# Power_Management.net
KiCad netlist of a schematic drawn in Altium Designer
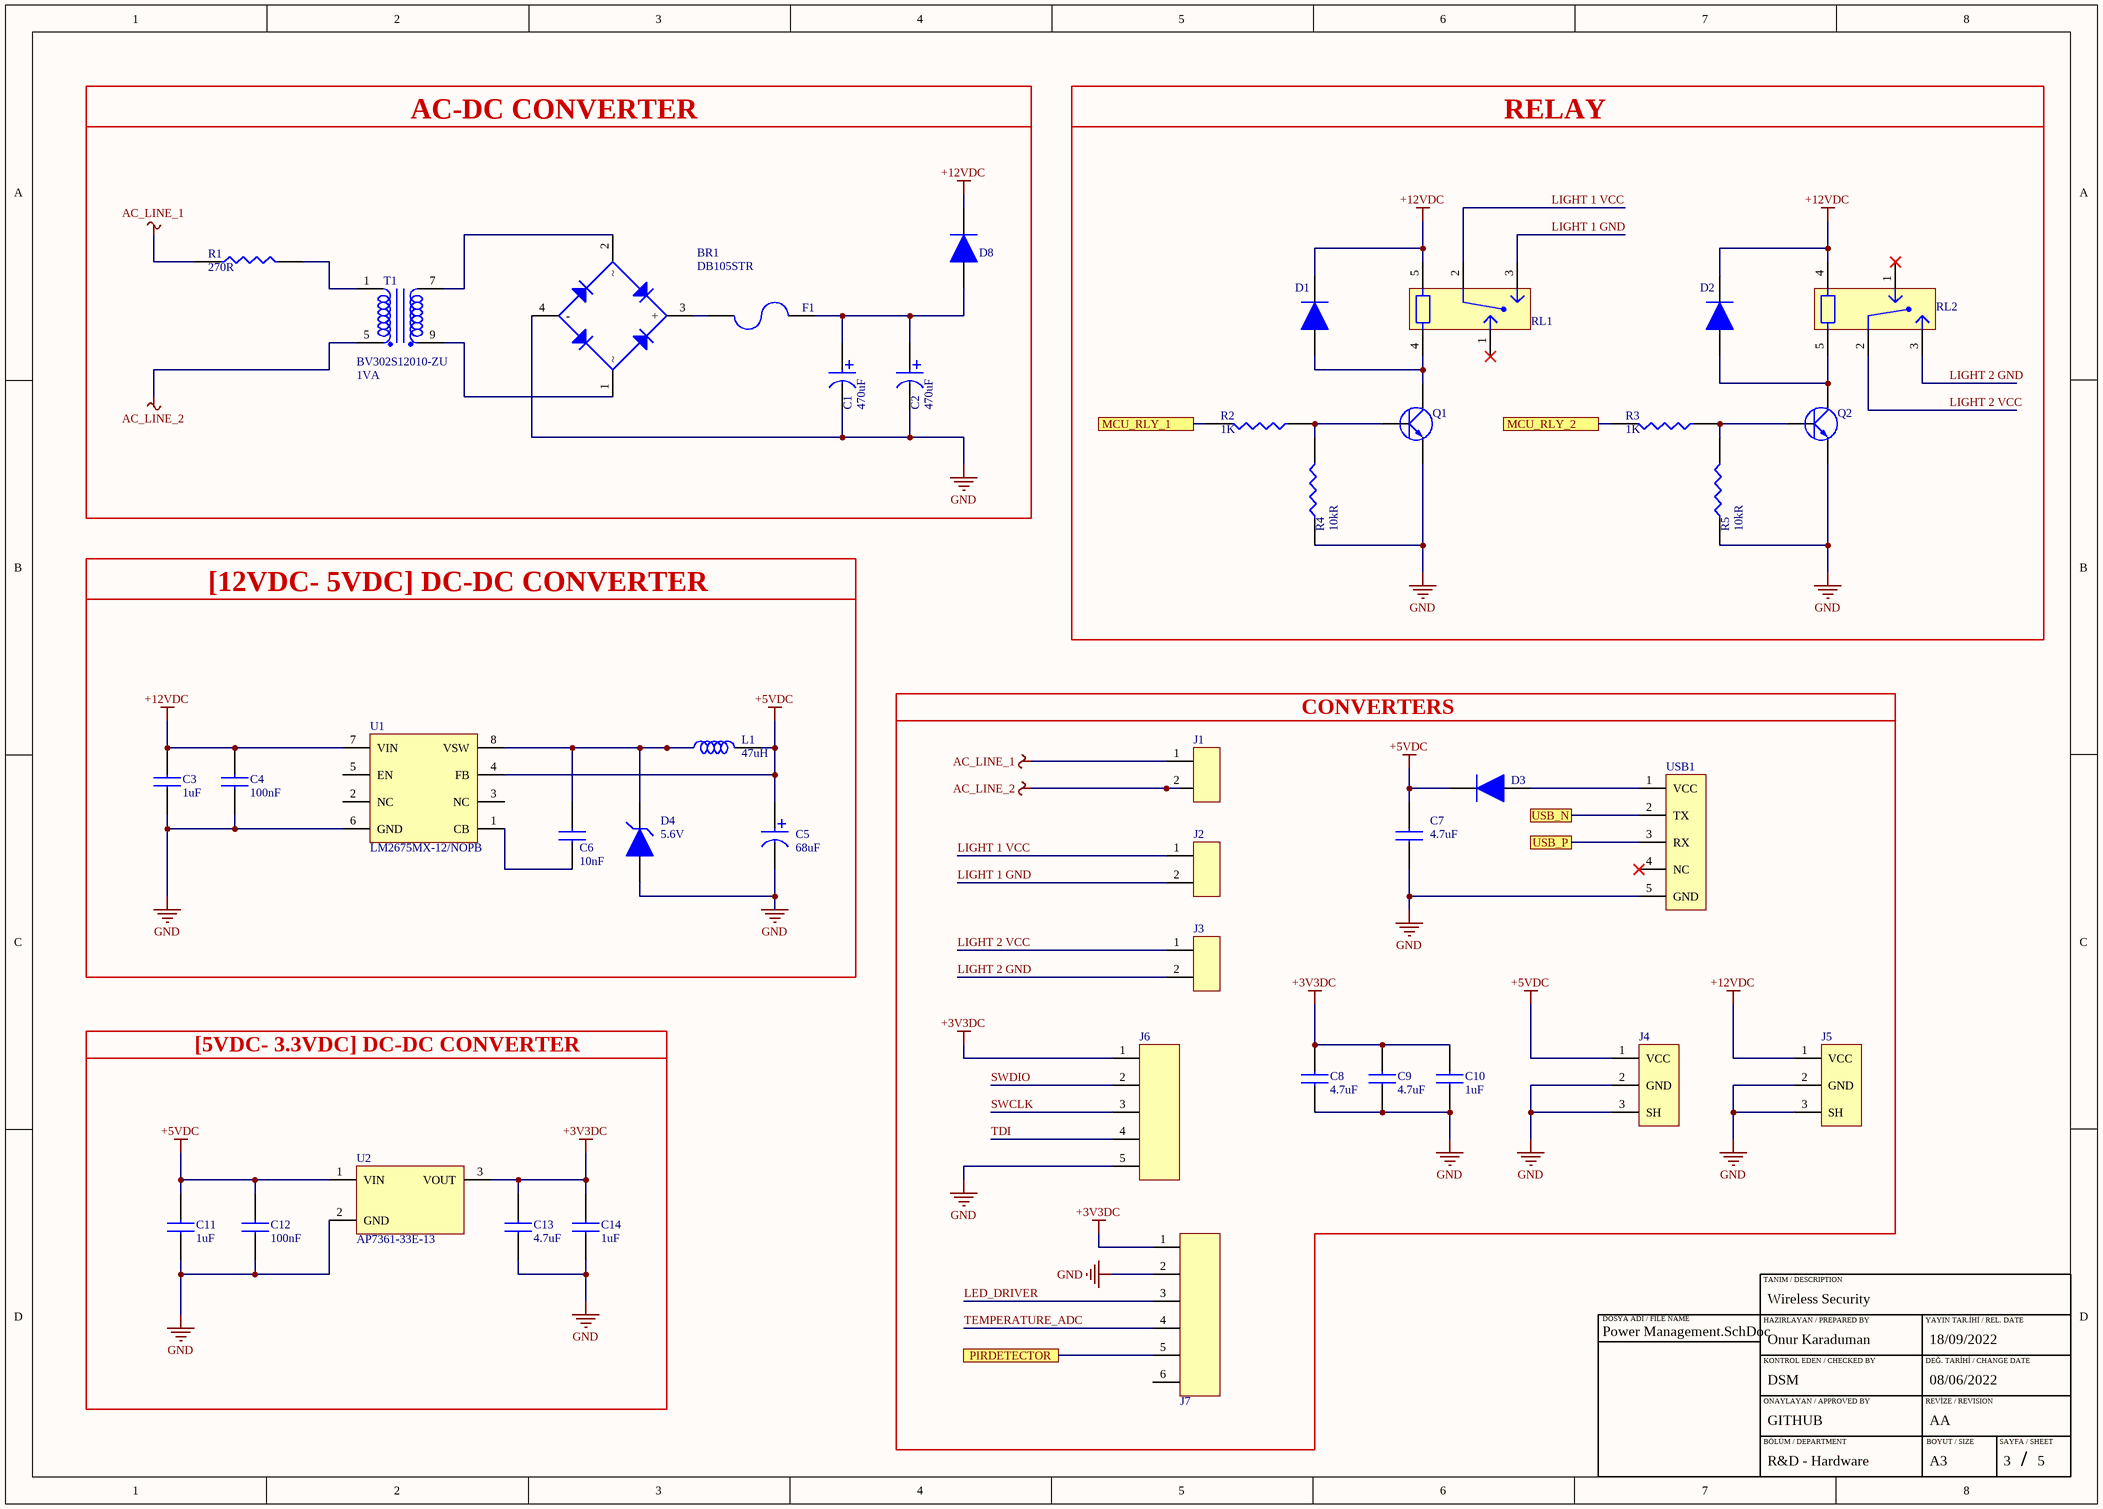
[diagram p0: Power Management.SchDoc]

(export (version "E")
  (design (tool "Eeschema 10.0.6"))
  (components
    (comp (ref "BR1")
      (value "DB105STR")
      (footprint "DB105STR")
      (description "Bridge Rect 1PHASE 600V 1A Db-s")
      (fields
        (field (name "MANUFACTURER") "Sangdest Microelectronics")
        (field (name "DESIGNED BY") "Onur Karaduman")
      )
      (libsource (lib "Ders1Lib") (part "DB105STR"))
    )
    (comp (ref "C1")
      (value "ESH477M050AH4AA")
      (footprint "ESH477M050AH4AA")
      (description "Cap, 470UF, 50V, Alu Elec, Radial")
      (fields
        (field (name "MANUFACTURER") "KEMET")
        (field (name "TOLERANCE") "20%")
        (field (name "CAPACITANCE") "470uF")
        (field (name "DESIGNED BY") "Onur Karaduman")
      )
      (libsource (lib "Ders1Lib") (part "ESH477M050AH4AA"))
    )
    (comp (ref "C2")
      (value "ESH477M050AH4AA")
      (footprint "ESH477M050AH4AA")
      (description "Cap, 470UF, 50V, Alu Elec, Radial")
      (fields
        (field (name "MANUFACTURER") "KEMET")
        (field (name "TOLERANCE") "20%")
        (field (name "CAPACITANCE") "470uF")
        (field (name "DESIGNED BY") "Onur Karaduman")
      )
      (libsource (lib "Ders1Lib") (part "ESH477M050AH4AA"))
    )
    (comp (ref "C3")
      (value "CL21B105KBFNNNE")
      (footprint "CAP_0805")
      (description "CAP CER 1UF 50V X7R 0805")
      (fields
        (field (name "MANUFACTURER") "Samsung")
        (field (name "TOLERANCE") "10%")
        (field (name "CAPACITANCE") "1uF")
        (field (name "DESIGNED BY") "Onur Karaduman")
      )
      (libsource (lib "Ders1Lib") (part "CAP CER 1uF 0805"))
    )
    (comp (ref "C4")
      (value "CL21B104KBCNNNC")
      (footprint "CAP_0805")
      (description "CAP CER 0.1UF 50V X7R 0805")
      (fields
        (field (name "MANUFACTURER") "Samsung")
        (field (name "TOLERANCE") "10%")
        (field (name "CAPACITANCE") "100nF")
        (field (name "DESIGNED BY") "Onur Karaduman")
      )
      (libsource (lib "Ders1Lib") (part "CAP CER 100nF 0805"))
    )
    (comp (ref "C5")
      (value "EEV686M035A9HAA")
      (footprint "CAP_EEVSERIES")
      (description "Cap Aluminum Lytic 68uF 35V 20% (6.3 X 7.7mm) SMD 280mA 2000h 105C T/R")
      (fields
        (field (name "MANUFACTURER") "KEMET")
        (field (name "TOLERANCE") "20%")
        (field (name "CAPACITANCE") "68uF")
        (field (name "DESIGNED BY") "Onur Karaduman")
      )
      (libsource (lib "Ders1Lib") (part "EEV686M035A9HAA"))
    )
    (comp (ref "C6")
      (value "0603B103K160CT")
      (footprint "CAP_0603")
      (description "Multilayer Ceramic Capacitor, 0.01 F, 10%, X7R, 16 V, 0603 [1608 Metric] RoHS Compliant: Yes")
      (fields
        (field (name "MANUFACTURER") "Walsin Technologies")
        (field (name "TOLERANCE") "10%")
        (field (name "CAPACITANCE") "10nF")
        (field (name "DESIGNED BY") "Onur Karaduman")
      )
      (libsource (lib "Ders1Lib") (part "CAP CER 10nF 0603"))
    )
    (comp (ref "C7")
      (value "CL21A475KAQNNNE")
      (footprint "CAP_0805")
      (description "CAP CER 4.7UF 25V X5R 0805")
      (fields
        (field (name "MANUFACTURER") "Samsung")
        (field (name "TOLERANCE") "10%")
        (field (name "CAPACITANCE") "4.7uF")
        (field (name "DESIGNED BY") "Onur Karaduman")
      )
      (libsource (lib "Ders1Lib") (part "CAP CER 4.7uF 0805"))
    )
    (comp (ref "C8")
      (value "CL21A475KAQNNNE")
      (footprint "CAP_0805")
      (description "CAP CER 4.7UF 25V X5R 0805")
      (fields
        (field (name "MANUFACTURER") "Samsung")
        (field (name "TOLERANCE") "10%")
        (field (name "CAPACITANCE") "4.7uF")
        (field (name "DESIGNED BY") "Onur Karaduman")
      )
      (libsource (lib "Ders1Lib") (part "CAP CER 4.7uF 0805"))
    )
    (comp (ref "C9")
      (value "CL21A475KAQNNNE")
      (footprint "CAP_0805")
      (description "CAP CER 4.7UF 25V X5R 0805")
      (fields
        (field (name "MANUFACTURER") "Samsung")
        (field (name "TOLERANCE") "10%")
        (field (name "CAPACITANCE") "4.7uF")
        (field (name "DESIGNED BY") "Onur Karaduman")
      )
      (libsource (lib "Ders1Lib") (part "CAP CER 4.7uF 0805"))
    )
    (comp (ref "C10")
      (value "CL21B105KBFNNNE")
      (footprint "CAP_0805")
      (description "CAP CER 1UF 50V X7R 0805")
      (fields
        (field (name "MANUFACTURER") "Samsung")
        (field (name "TOLERANCE") "10%")
        (field (name "CAPACITANCE") "1uF")
        (field (name "DESIGNED BY") "Onur Karaduman")
      )
      (libsource (lib "Ders1Lib") (part "CAP CER 1uF 0805"))
    )
    (comp (ref "C11")
      (value "CL21B105KBFNNNE")
      (footprint "CAP_0805")
      (description "CAP CER 1UF 50V X7R 0805")
      (fields
        (field (name "MANUFACTURER") "Samsung")
        (field (name "TOLERANCE") "10%")
        (field (name "CAPACITANCE") "1uF")
        (field (name "DESIGNED BY") "Onur Karaduman")
      )
      (libsource (lib "Ders1Lib") (part "CAP CER 1uF 0805"))
    )
    (comp (ref "C12")
      (value "C0603C104K4RACTU")
      (footprint "CAP_0603")
      (description "Cap Cer 0.1uF 16V X7R 10% SMD 0603 125°C Paper T/R")
      (fields
        (field (name "MANUFACTURER") "KEMET")
        (field (name "TOLERANCE") "10%")
        (field (name "CAPACITANCE") "100nF")
        (field (name "DESIGNED BY") "Onur Karaduman")
      )
      (libsource (lib "Ders1Lib") (part "CAP CER 100nF 0603"))
    )
    (comp (ref "C13")
      (value "CL21A475KAQNNNE")
      (footprint "CAP_0805")
      (description "CAP CER 4.7UF 25V X5R 0805")
      (fields
        (field (name "MANUFACTURER") "Samsung")
        (field (name "TOLERANCE") "10%")
        (field (name "CAPACITANCE") "4.7uF")
        (field (name "DESIGNED BY") "Onur Karaduman")
      )
      (libsource (lib "Ders1Lib") (part "CAP CER 4.7uF 0805"))
    )
    (comp (ref "C14")
      (value "CL21B105KBFNNNE")
      (footprint "CAP_0805")
      (description "CAP CER 1UF 50V X7R 0805")
      (fields
        (field (name "MANUFACTURER") "Samsung")
        (field (name "TOLERANCE") "10%")
        (field (name "CAPACITANCE") "1uF")
        (field (name "DESIGNED BY") "Onur Karaduman")
      )
      (libsource (lib "Ders1Lib") (part "CAP CER 1uF 0805"))
    )
    (comp (ref "D1")
      (value "1N4148WS")
      (footprint "SOD32-F")
      (description "VR=75V IF=150mA Trr=4ns P=200mW")
      (fields
        (field (name "MANUFACTURER") "ON Semiconductor / Fairchild")
        (field (name "DESIGNED BY") "Onur Karaduman")
      )
      (libsource (lib "Ders1Lib") (part "1N4148WS"))
    )
    (comp (ref "D2")
      (value "1N4148WS")
      (footprint "SOD32-F")
      (description "VR=75V IF=150mA Trr=4ns P=200mW")
      (fields
        (field (name "MANUFACTURER") "ON Semiconductor / Fairchild")
        (field (name "DESIGNED BY") "Onur Karaduman")
      )
      (libsource (lib "Ders1Lib") (part "1N4148WS"))
    )
    (comp (ref "D3")
      (value "1N4148WS")
      (footprint "SOD32-F")
      (description "VR=75V IF=150mA Trr=4ns P=200mW")
      (fields
        (field (name "MANUFACTURER") "ON Semiconductor / Fairchild")
        (field (name "DESIGNED BY") "Onur Karaduman")
      )
      (libsource (lib "Ders1Lib") (part "1N4148WS"))
    )
    (comp (ref "D4")
      (value "1SMB5919BT3G")
      (footprint "SMB")
      (description "Vz=5.6V 5.32V~5.88V Izt=66.9mA")
      (fields
        (field (name "MANUFACTURER") "ON Semiconductor")
        (field (name "TOLERANCE") "5%")
        (field (name "ZENER VOLTAGE") "5.6V")
        (field (name "DESIGNED BY") "Onur Karaduman")
      )
      (libsource (lib "Ders1Lib") (part "1SMB5919BT3G"))
    )
    (comp (ref "D8")
      (value "1N4148WS")
      (footprint "SOD32-F")
      (description "VR=75V IF=150mA Trr=4ns P=200mW")
      (fields
        (field (name "MANUFACTURER") "ON Semiconductor / Fairchild")
        (field (name "DESIGNED BY") "Onur Karaduman")
      )
      (libsource (lib "Ders1Lib") (part "1N4148WS"))
    )
    (comp (ref "F1")
      (value "3413.0216.22")
      (footprint "3413.0216.22")
      (description "Fuse Chip Fast Acting 1A 32V SMD Solder Pad 1206 Glass T/R VDE/cULus")
      (fields (field (name "MANUFACTURER") "Schurter") (field (name "DESIGNED BY") "Onur Karaduman"))
      (libsource (lib "Ders1Lib") (part "3413.0216.22"))
    )
    (comp (ref "J1")
      (value "TBP01R1-508-02BE")
      (footprint "TBP01R1-508")
      (description "2~24 Poles, Pluggable, Receptacle, Horizontal, 5.08 Pitch, Terminal Block Connector")
      (fields (field (name "MANUFACTURER") "CUI Devices") (field (name "DESIGNED BY") "Onur Karaduman"))
      (libsource (lib "Ders1Lib") (part "TBP01R1-508-02BE"))
    )
    (comp (ref "J2")
      (value "TBP01R1-508-02BE")
      (footprint "TBP01R1-508")
      (description "2~24 Poles, Pluggable, Receptacle, Horizontal, 5.08 Pitch, Terminal Block Connector")
      (fields (field (name "MANUFACTURER") "CUI Devices") (field (name "DESIGNED BY") "Onur Karaduman"))
      (libsource (lib "Ders1Lib") (part "TBP01R1-508-02BE"))
    )
    (comp (ref "J3")
      (value "TBP01R1-508-02BE")
      (footprint "TBP01R1-508")
      (description "2~24 Poles, Pluggable, Receptacle, Horizontal, 5.08 Pitch, Terminal Block Connector")
      (fields (field (name "MANUFACTURER") "CUI Devices") (field (name "DESIGNED BY") "Onur Karaduman"))
      (libsource (lib "Ders1Lib") (part "TBP01R1-508-02BE"))
    )
    (comp (ref "J4")
      (value "PJ-037AH-SMT-TR")
      (footprint "JACK")
      (description "2.0 x 6.3 mm, 5.0 A, Horizontal, Surface Mount (SMT), Dc Power Jack Connector")
      (fields (field (name "MANUFACTURER") "CUI") (field (name "DESIGNED BY") "Onur Karaduman"))
      (libsource (lib "Ders1Lib") (part "PJ-037AH-SMT-TR"))
    )
    (comp (ref "J5")
      (value "PJ-037AH-SMT-TR")
      (footprint "JACK")
      (description "2.0 x 6.3 mm, 5.0 A, Horizontal, Surface Mount (SMT), Dc Power Jack Connector")
      (fields (field (name "MANUFACTURER") "CUI") (field (name "DESIGNED BY") "Onur Karaduman"))
      (libsource (lib "Ders1Lib") (part "PJ-037AH-SMT-TR"))
    )
    (comp (ref "J6")
      (value "SMH-105-02-L-S")
      (footprint "SMH-105-02-L-S")
      (description ".100 C.L. HORIZONTAL SMT SOCKET")
      (fields (field (name "MANUFACTURER") "Samtec") (field (name "DESIGNED BY") "Onur Karaduman"))
      (libsource (lib "Ders1Lib") (part "SMH-105-02-L-S"))
    )
    (comp (ref "J7")
      (value "64800611622")
      (footprint "64800611622")
      (description "Conn, Header, 6POS, 1ROW, 1.5MM;")
      (fields (field (name "MANUFACTURER") "Wurth Electronics") (field (name "DESIGNED BY") "Onur Karaduman"))
      (libsource (lib "Ders1Lib") (part "64800611622"))
    )
    (comp (ref "L1")
      (value "78438335470")
      (footprint "IND_1212")
      (description "Fixed Ind 47UH 390MA 2.3 Ohm SMD")
      (fields
        (field (name "MANUFACTURER") "Wurth Electronics")
        (field (name "TOLERANCE") "30%")
        (field (name "INDUCTANCE") "47uH")
        (field (name "DESIGNED BY") "Onur Karaduman")
      )
      (libsource (lib "Ders1Lib") (part "78438335470"))
    )
    (comp (ref "Q1")
      (value "MMBT3904-7-F")
      (footprint "SOT23-F")
      (description "NPN Ic=200mA Vceo=40V hfe=100~300 fT=310MHz P=300mW SOT-23")
      (fields (field (name "MANUFACTURER") "Diodes Zetex") (field (name "DESIGNED BY") "Onur Karaduman"))
      (libsource (lib "Ders1Lib") (part "MMBT3904-7-F"))
    )
    (comp (ref "Q2")
      (value "MMBT3904-7-F")
      (footprint "SOT23-F")
      (description "NPN Ic=200mA Vceo=40V hfe=100~300 fT=310MHz P=300mW SOT-23")
      (fields (field (name "MANUFACTURER") "Diodes Zetex") (field (name "DESIGNED BY") "Onur Karaduman"))
      (libsource (lib "Ders1Lib") (part "MMBT3904-7-F"))
    )
    (comp (ref "R1")
      (value "5WD27")
      (footprint "RES_AXIAL_W")
      (description "Resistor 5 Watt Cermet Wirewound Flameproof .27 Ohm 5% Axial Lead")
      (fields
        (field (name "MANUFACTURER") "NTE Electronics")
        (field (name "TOLERANCE") "5%")
        (field (name "RESISTANCE") "270R")
        (field (name "DESIGNED BY") "Onur Karaduman")
      )
      (libsource (lib "Ders1Lib") (part "5WD27"))
    )
    (comp (ref "R2")
      (value "RES 1K OHM 0603")
      (footprint "RES_0603")
      (description "Res Thick Film 0603 1K Ohm 1% 0.25W(1/4W) ±100ppm/°C Epoxy Resin Pad SMD Automotive T/R")
      (fields
        (field (name "MANUFACTURER") "Rohm")
        (field (name "MANUFACTURER PART NUMBER") "ESR03EZPF1001")
        (field (name "RESISTANCE") "1K")
        (field (name "DESIGNED BY") "Onur Karaduman")
      )
      (libsource (lib "Ders1Lib") (part "RES 1K OHM 0603"))
    )
    (comp (ref "R3")
      (value "RES 1K OHM 0603")
      (footprint "RES_0603")
      (description "Res Thick Film 0603 1K Ohm 1% 0.25W(1/4W) ±100ppm/°C Epoxy Resin Pad SMD Automotive T/R")
      (fields
        (field (name "MANUFACTURER") "Rohm")
        (field (name "MANUFACTURER PART NUMBER") "ESR03EZPF1001")
        (field (name "RESISTANCE") "1K")
        (field (name "DESIGNED BY") "Onur Karaduman")
      )
      (libsource (lib "Ders1Lib") (part "RES 1K OHM 0603"))
    )
    (comp (ref "R4")
      (value "RC0603FR-0710KL")
      (footprint "RES_0603")
      (description "RES SMD 10K OHM 1% 1/10W 0603")
      (fields
        (field (name "MANUFACTURER") "Yageo")
        (field (name "TOLERANCE") "1%")
        (field (name "RESISTANCE") "10kR")
        (field (name "DESIGNED BY") "Onur Karaduman")
      )
      (libsource (lib "Ders1Lib") (part "RES 10K OHM 0603"))
    )
    (comp (ref "R5")
      (value "RC0603FR-0710KL")
      (footprint "RES_0603")
      (description "RES SMD 10K OHM 1% 1/10W 0603")
      (fields
        (field (name "MANUFACTURER") "Yageo")
        (field (name "TOLERANCE") "1%")
        (field (name "RESISTANCE") "10kR")
        (field (name "DESIGNED BY") "Onur Karaduman")
      )
      (libsource (lib "Ders1Lib") (part "RES 10K OHM 0603"))
    )
    (comp (ref "RL1")
      (value "ALQ112")
      (footprint "ALQ112")
      (description "General Purpose Relay SPDT (1 Form C) 12VDC Coil Through Hole")
      (fields (field (name "MANUFACTURER") "Panasonic") (field (name "DESIGNED BY") "Onur Karaduman"))
      (libsource (lib "Ders1Lib") (part "ALQ112"))
    )
    (comp (ref "RL2")
      (value "ALQ112")
      (footprint "ALQ112")
      (description "General Purpose Relay SPDT (1 Form C) 12VDC Coil Through Hole")
      (fields (field (name "MANUFACTURER") "Panasonic") (field (name "DESIGNED BY") "Onur Karaduman"))
      (libsource (lib "") (part "ALQ112_1"))
    )
    (comp (ref "T1")
      (value "BV302S12010-ZU")
      (footprint "BV302S12010-ZU")
      (description "Pwr Xfmr Laminated 1VA Th")
      (fields
        (field (name "MANUFACTURER") "Zettler Magnetics")
        (field (name "RATED POWER") "1VA")
        (field (name "DESIGNED BY") "Onur Karaduman")
      )
      (libsource (lib "Ders1Lib") (part "BV302S12010-ZU"))
    )
    (comp (ref "U1")
      (value "LM2675MX-12/NOPB")
      (footprint "SOIC 8")
      (description "SIMPLE SWITCHER® 6.5V to 40V, 1A Low Component Count Step-Down Regulator 8-SOIC -40 to 125")
      (fields
        (field (name "MANUFACTURER") "TI National Semiconductor")
        (field (name "DESIGNED BY") "Onur Karaduman")
      )
      (libsource (lib "Ders1Lib") (part "LM2675MX-12/NOPB"))
    )
    (comp (ref "U2")
      (value "AP7361-33E-13")
      (footprint "SOT223")
      (description "AP7361 Series 3.3 V 1 A Low SMT Dropout Fixed-Mode Regulator - SOT-223")
      (fields (field (name "MANUFACTURER") "Diodes") (field (name "DESIGNED BY") "Onur Karaduman"))
      (libsource (lib "Ders1Lib") (part "AP7361-33E-13"))
    )
    (comp (ref "USB1")
      (value "10118192-0001LF")
      (footprint "MICRO_B_USB")
      (description "CONN USB MICRO B RECPT SMT R/A")
      (fields
        (field (name "MANUFACTURER") "Amphenol ICC / FCI")
        (field (name "DESIGNED BY") "Onur Karaduman")
      )
      (libsource (lib "Ders1Lib") (part "Micro B USB Connector"))
    )
  )
  (nets
    (net (code "1") (name "+3V3DC") (class "Default")
      (node (ref "C10") (pin "2") (pintype "passive"))
      (node (ref "C13") (pin "2") (pintype "passive"))
      (node (ref "C14") (pin "2") (pintype "passive"))
      (node (ref "C8") (pin "2") (pintype "passive"))
      (node (ref "C9") (pin "2") (pintype "passive"))
      (node (ref "J6") (pin "1") (pintype "passive"))
      (node (ref "J7") (pin "1") (pintype "passive"))
      (node (ref "U2") (pin "3") (pinfunction "VOUT_3") (pintype "passive"))
    )
    (net (code "2") (name "+5VDC") (class "Default")
      (node (ref "C11") (pin "2") (pintype "passive"))
      (node (ref "C12") (pin "2") (pintype "passive"))
      (node (ref "C5") (pin "1") (pintype "passive"))
      (node (ref "C7") (pin "2") (pintype "passive"))
      (node (ref "D3") (pin "1") (pintype "passive"))
      (node (ref "J4") (pin "1") (pinfunction "VCC_1") (pintype "passive"))
      (node (ref "L1") (pin "2") (pintype "passive"))
      (node (ref "U1") (pin "4") (pinfunction "FB_4") (pintype "passive"))
      (node (ref "U2") (pin "1") (pinfunction "VIN_1") (pintype "passive"))
    )
    (net (code "3") (name "+12VDC") (class "Default")
      (node (ref "C3") (pin "2") (pintype "passive"))
      (node (ref "C4") (pin "2") (pintype "passive"))
      (node (ref "D1") (pin "1") (pintype "passive"))
      (node (ref "D2") (pin "1") (pintype "passive"))
      (node (ref "D8") (pin "1") (pintype "passive"))
      (node (ref "J5") (pin "1") (pinfunction "VCC_1") (pintype "passive"))
      (node (ref "RL1") (pin "5") (pinfunction "5_5") (pintype "passive"))
      (node (ref "RL2") (pin "4") (pinfunction "4_4") (pintype "passive"))
      (node (ref "U1") (pin "7") (pinfunction "VIN_7") (pintype "passive"))
    )
    (net (code "4") (name "/LED_DRIVER") (class "Default") (node (ref "J7") (pin "3") (pintype "passive")))
    (net (code "5") (name "/LIGHT 1 GND") (class "Default")
      (node (ref "J2") (pin "2") (pintype "passive"))
      (node (ref "RL1") (pin "3") (pinfunction "3_3") (pintype "passive"))
    )
    (net (code "6") (name "/LIGHT 1 VCC") (class "Default")
      (node (ref "J2") (pin "1") (pintype "passive"))
      (node (ref "RL1") (pin "2") (pinfunction "2_2") (pintype "passive"))
    )
    (net (code "7") (name "/LIGHT 2 GND") (class "Default")
      (node (ref "J3") (pin "2") (pintype "passive"))
      (node (ref "RL2") (pin "3") (pinfunction "3_3") (pintype "passive"))
    )
    (net (code "8") (name "/LIGHT 2 VCC") (class "Default")
      (node (ref "J3") (pin "1") (pintype "passive"))
      (node (ref "RL2") (pin "2") (pinfunction "2_2") (pintype "passive"))
    )
    (net (code "9") (name "/MCU_RLY_1") (class "Default") (node (ref "R2") (pin "2") (pintype "passive")))
    (net (code "10") (name "/MCU_RLY_2") (class "Default") (node (ref "R3") (pin "2") (pintype "passive")))
    (net (code "11") (name "/PIRDETECTOR") (class "Default") (node (ref "J7") (pin "5") (pintype "passive")))
    (net (code "12") (name "/SWCLK") (class "Default") (node (ref "J6") (pin "3") (pintype "passive")))
    (net (code "13") (name "/SWDIO") (class "Default") (node (ref "J6") (pin "2") (pintype "passive")))
    (net (code "14") (name "/TDI") (class "Default") (node (ref "J6") (pin "4") (pintype "passive")))
    (net (code "15") (name "/TEMPERATURE_ADC") (class "Default")
      (node (ref "J7") (pin "4") (pintype "passive"))
    )
    (net (code "16") (name "/USB_N") (class "Default")
      (node (ref "USB1") (pin "2") (pinfunction "TX_2") (pintype "passive"))
    )
    (net (code "17") (name "/USB_P") (class "Default")
      (node (ref "USB1") (pin "3") (pinfunction "RX_3") (pintype "passive"))
    )
    (net (code "18") (name "AC_LINE_1") (class "Default")
      (node (ref "J1") (pin "1") (pintype "passive"))
      (node (ref "R1") (pin "1") (pintype "passive"))
    )
    (net (code "19") (name "AC_LINE_2") (class "Default")
      (node (ref "J1") (pin "2") (pintype "passive"))
      (node (ref "T1") (pin "5") (pinfunction "5_5") (pintype "passive"))
    )
    (net (code "20") (name "GND") (class "Default")
      (node (ref "BR1") (pin "4") (pinfunction "-_4") (pintype "passive"))
      (node (ref "C1") (pin "2") (pintype "passive"))
      (node (ref "C10") (pin "1") (pintype "passive"))
      (node (ref "C11") (pin "1") (pintype "passive"))
      (node (ref "C12") (pin "1") (pintype "passive"))
      (node (ref "C13") (pin "1") (pintype "passive"))
      (node (ref "C14") (pin "1") (pintype "passive"))
      (node (ref "C2") (pin "2") (pintype "passive"))
      (node (ref "C3") (pin "1") (pintype "passive"))
      (node (ref "C4") (pin "1") (pintype "passive"))
      (node (ref "C5") (pin "2") (pintype "passive"))
      (node (ref "C7") (pin "1") (pintype "passive"))
      (node (ref "C8") (pin "1") (pintype "passive"))
      (node (ref "C9") (pin "1") (pintype "passive"))
      (node (ref "D4") (pin "1") (pinfunction "1_1") (pintype "passive"))
      (node (ref "J4") (pin "2") (pinfunction "GND_2") (pintype "passive"))
      (node (ref "J4") (pin "3") (pinfunction "SH_3") (pintype "passive"))
      (node (ref "J5") (pin "2") (pinfunction "GND_2") (pintype "passive"))
      (node (ref "J5") (pin "3") (pinfunction "SH_3") (pintype "passive"))
      (node (ref "J6") (pin "5") (pintype "passive"))
      (node (ref "J7") (pin "2") (pintype "passive"))
      (node (ref "Q1") (pin "2") (pinfunction "2_2") (pintype "passive"))
      (node (ref "Q2") (pin "2") (pinfunction "2_2") (pintype "passive"))
      (node (ref "R4") (pin "1") (pintype "passive"))
      (node (ref "R5") (pin "1") (pintype "passive"))
      (node (ref "U1") (pin "6") (pinfunction "GND_6") (pintype "passive"))
      (node (ref "U2") (pin "2") (pinfunction "GND_2") (pintype "passive"))
      (node (ref "USB1") (pin "5") (pinfunction "GND_5") (pintype "passive"))
    )
    (net (code "21") (name "Net-(BR1-+)") (class "Default")
      (node (ref "BR1") (pin "3") (pinfunction "+_3") (pintype "passive"))
      (node (ref "F1") (pin "1") (pintype "passive"))
    )
    (net (code "22") (name "Net-(BR1-~-Pad1)") (class "Default")
      (node (ref "BR1") (pin "1") (pinfunction "~_1") (pintype "passive"))
      (node (ref "T1") (pin "9") (pinfunction "9_9") (pintype "passive"))
    )
    (net (code "23") (name "Net-(BR1-~-Pad2)") (class "Default")
      (node (ref "BR1") (pin "2") (pinfunction "~_2") (pintype "passive"))
      (node (ref "T1") (pin "7") (pinfunction "7_7") (pintype "passive"))
    )
    (net (code "24") (name "Net-(C1-Pad1)") (class "Default")
      (node (ref "C1") (pin "1") (pintype "passive"))
      (node (ref "C2") (pin "1") (pintype "passive"))
      (node (ref "D8") (pin "2") (pinfunction "2_2") (pintype "passive"))
      (node (ref "F1") (pin "2") (pintype "passive"))
    )
    (net (code "25") (name "Net-(Q1-Pad1)") (class "Default")
      (node (ref "Q1") (pin "1") (pinfunction "1_1") (pintype "passive"))
      (node (ref "R2") (pin "1") (pintype "passive"))
      (node (ref "R4") (pin "2") (pintype "passive"))
    )
    (net (code "26") (name "Net-(Q1-_3)") (class "Default")
      (node (ref "D1") (pin "2") (pinfunction "2_2") (pintype "passive"))
      (node (ref "Q1") (pin "3") (pinfunction "_3_3") (pintype "passive"))
      (node (ref "RL1") (pin "4") (pinfunction "4_4") (pintype "passive"))
    )
    (net (code "27") (name "Net-(Q2-Pad1)") (class "Default")
      (node (ref "Q2") (pin "1") (pinfunction "1_1") (pintype "passive"))
      (node (ref "R3") (pin "1") (pintype "passive"))
      (node (ref "R5") (pin "2") (pintype "passive"))
    )
    (net (code "28") (name "Net-(Q2-_3)") (class "Default")
      (node (ref "D2") (pin "2") (pinfunction "2_2") (pintype "passive"))
      (node (ref "Q2") (pin "3") (pinfunction "_3_3") (pintype "passive"))
      (node (ref "RL2") (pin "5") (pinfunction "5_5") (pintype "passive"))
    )
    (net (code "29") (name "Net-(R1-Pad2)") (class "Default")
      (node (ref "R1") (pin "2") (pintype "passive"))
      (node (ref "T1") (pin "1") (pinfunction "1_1") (pintype "passive"))
    )
    (net (code "30") (name "Net-(U1-CB)") (class "Default")
      (node (ref "C6") (pin "1") (pintype "passive"))
      (node (ref "U1") (pin "1") (pinfunction "CB_1") (pintype "passive"))
    )
    (net (code "31") (name "Net-(U1-VSW)") (class "Default")
      (node (ref "C6") (pin "2") (pintype "passive"))
      (node (ref "D4") (pin "2") (pinfunction "2_2") (pintype "passive"))
      (node (ref "L1") (pin "1") (pinfunction "1_1") (pintype "passive"))
      (node (ref "U1") (pin "8") (pinfunction "VSW_8") (pintype "passive"))
    )
    (net (code "32") (name "Net-(USB1-VCC)") (class "Default")
      (node (ref "D3") (pin "2") (pinfunction "2_2") (pintype "passive"))
      (node (ref "USB1") (pin "1") (pinfunction "VCC_1") (pintype "passive"))
    )
    (net (code "33") (name "unconnected-(J7-Pad6)") (class "Default")
      (node (ref "J7") (pin "6") (pintype "passive"))
    )
    (net (code "34") (name "unconnected-(RL1-Pad1)") (class "Default")
      (node (ref "RL1") (pin "1") (pinfunction "1_1") (pintype "passive"))
    )
    (net (code "35") (name "unconnected-(RL2-Pad1)") (class "Default")
      (node (ref "RL2") (pin "1") (pinfunction "1_1") (pintype "passive"))
    )
    (net (code "36") (name "unconnected-(U1-EN-Pad5)") (class "Default")
      (node (ref "U1") (pin "5") (pinfunction "EN_5") (pintype "passive"))
    )
    (net (code "37") (name "unconnected-(U1-NC-Pad2)") (class "Default")
      (node (ref "U1") (pin "2") (pinfunction "NC_2") (pintype "passive"))
    )
    (net (code "38") (name "unconnected-(U1-NC-Pad3)") (class "Default")
      (node (ref "U1") (pin "3") (pinfunction "NC_3") (pintype "passive"))
    )
    (net (code "39") (name "unconnected-(USB1-NC-Pad4)") (class "Default")
      (node (ref "USB1") (pin "4") (pinfunction "NC_4") (pintype "passive+no_connect"))
    )
  )
)
